# PureRingMod.net
KiCad netlist of a schematic drawn in EAGLE
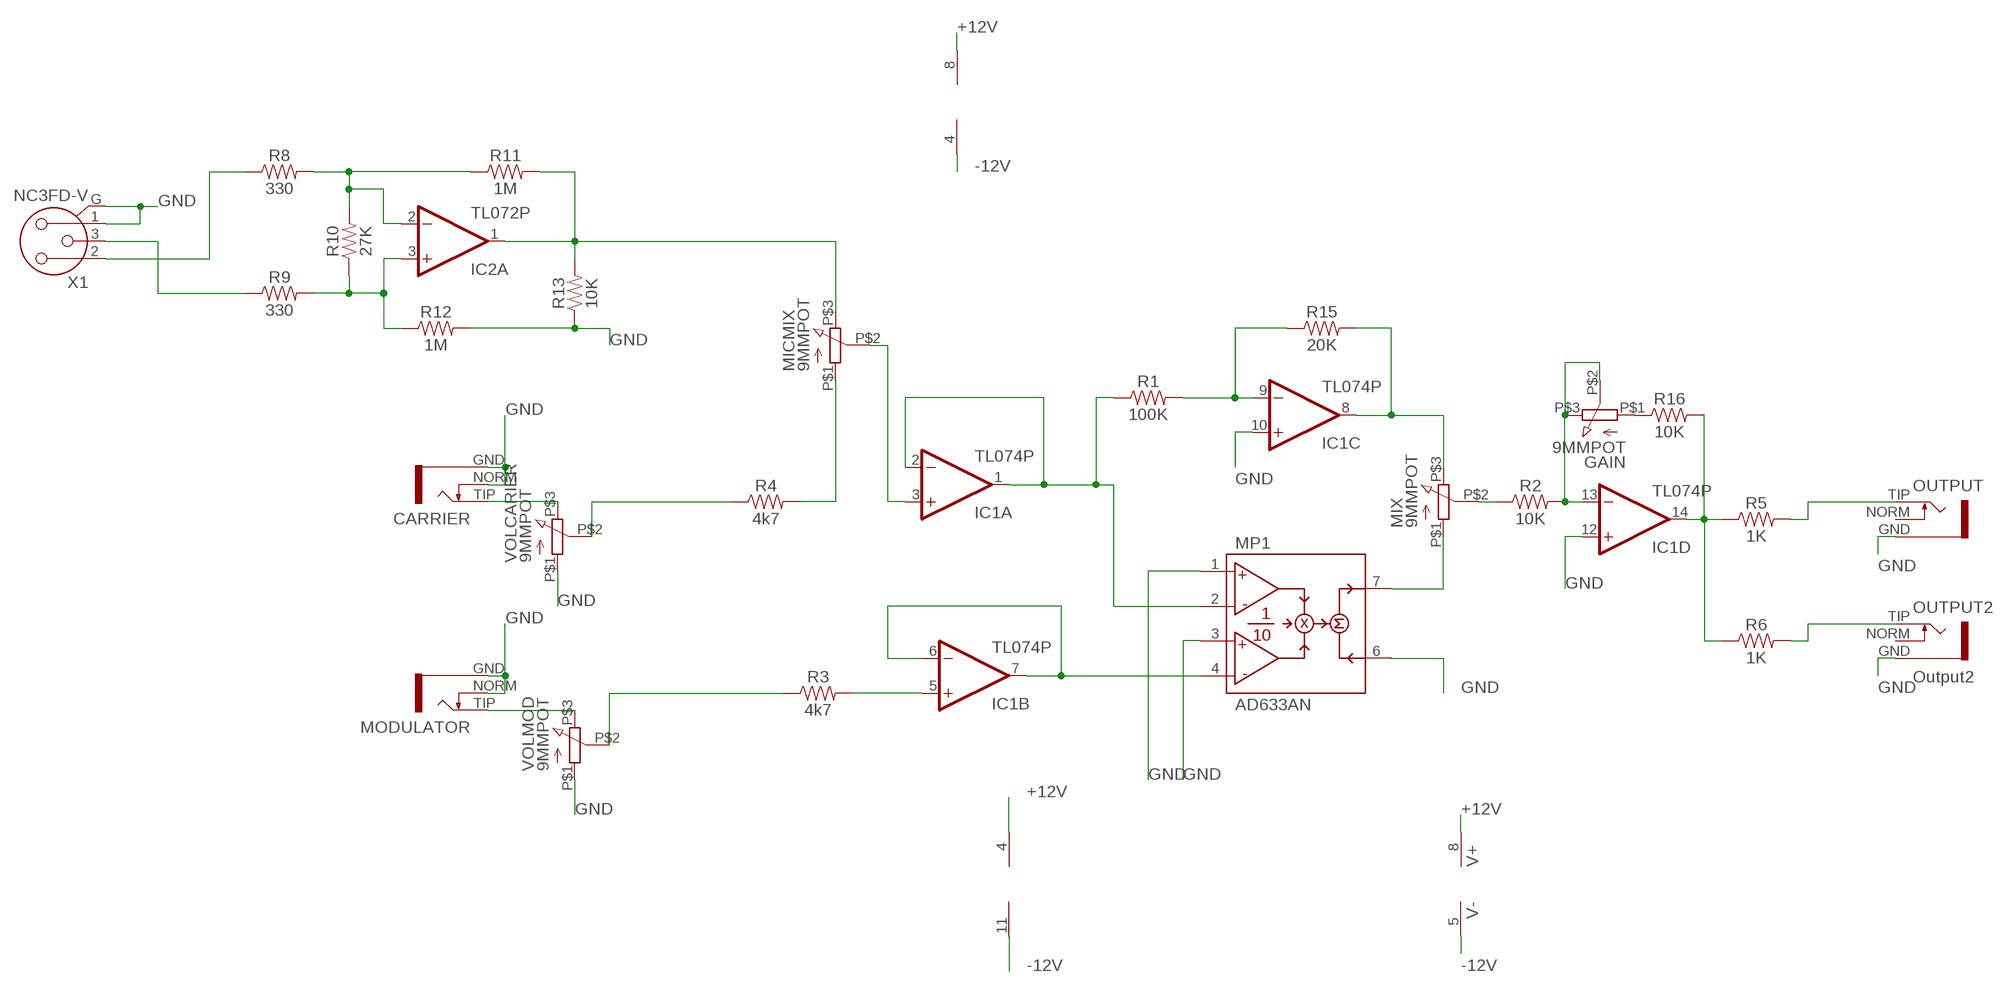
[diagram p0: schematic, sheet 1]
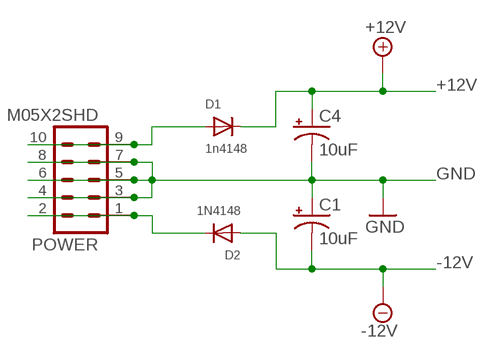
[diagram p1: schematic, sheet 2]

(export (version "E")
  (design (tool "Eeschema 10.0.6"))
  (components
    (comp (ref "C1")
      (value "10uF")
      (footprint "eagle-import:CPOL-RADIAL-2.5MM-5MM")
      (libsource (lib "eagle-import") (part "10UF-POLAR-RADIAL-2.5MM-25V-20%"))
    )
    (comp (ref "C4")
      (value "10uF")
      (footprint "eagle-import:CPOL-RADIAL-2.5MM-5MM")
      (libsource (lib "eagle-import") (part "10UF-POLAR-RADIAL-2.5MM-25V-20%"))
    )
    (comp (ref "D1")
      (value "1n4148")
      (footprint "eagle-import:DO-1N4148")
      (libsource (lib "eagle-import") (part "DIODEDO-1N4148"))
    )
    (comp (ref "D2")
      (value "1N4148")
      (footprint "eagle-import:DO-1N4148")
      (libsource (lib "eagle-import") (part "DIODEDO-1N4148"))
    )
    (comp (ref "POWER")
      (value "M05X2SHD")
      (footprint "eagle-import:2X5-SHROUDED")
      (libsource (lib "eagle-import") (part "M05X2SHD"))
    )
    (comp (ref "CARRIER")
      (value "S_JACK")
      (footprint "eagle-import:S_JACK")
      (libsource (lib "eagle-import") (part "S_JACK"))
    )
    (comp (ref "GAIN")
      (value "9MMPOT")
      (footprint "eagle-import:POT")
      (libsource (lib "eagle-import") (part "9MMPOT"))
    )
    (comp (ref "IC1")
      (value "TL074P")
      (footprint "eagle-import:DIL14")
      (libsource (lib "eagle-import") (part "TL074P"))
    )
    (comp (ref "IC2")
      (value "TL072P")
      (footprint "eagle-import:DIL08")
      (libsource (lib "eagle-import") (part "TL072P"))
    )
    (comp (ref "MICMIX")
      (value "9MMPOT")
      (footprint "eagle-import:POT")
      (libsource (lib "eagle-import") (part "9MMPOT"))
    )
    (comp (ref "MIX")
      (value "9MMPOT")
      (footprint "eagle-import:POT")
      (libsource (lib "eagle-import") (part "9MMPOT"))
    )
    (comp (ref "MODULATOR")
      (value "S_JACK")
      (footprint "eagle-import:S_JACK")
      (libsource (lib "eagle-import") (part "S_JACK"))
    )
    (comp (ref "MP1")
      (value "AD633AN")
      (footprint "eagle-import:DIL08")
      (libsource (lib "eagle-import") (part "AD633NA"))
    )
    (comp (ref "OUTPUT")
      (value "S_JACK")
      (footprint "eagle-import:S_JACK")
      (libsource (lib "eagle-import") (part "S_JACK"))
    )
    (comp (ref "OUTPUT2")
      (value "Output2")
      (footprint "eagle-import:S_JACK")
      (libsource (lib "eagle-import") (part "S_JACK"))
    )
    (comp (ref "R1")
      (value "100K")
      (footprint "eagle-import:AXIAL-0.3")
      (libsource (lib "eagle-import") (part "330OHM-HORIZ-1/10W-5%"))
    )
    (comp (ref "R2")
      (value "10K")
      (footprint "eagle-import:AXIAL-0.3")
      (libsource (lib "eagle-import") (part "330OHM-HORIZ-1/10W-5%"))
    )
    (comp (ref "R3")
      (value "4k7")
      (footprint "eagle-import:AXIAL-0.3")
      (libsource (lib "eagle-import") (part "330OHM-HORIZ-1/10W-5%"))
    )
    (comp (ref "R4")
      (value "4k7")
      (footprint "eagle-import:AXIAL-0.3")
      (libsource (lib "eagle-import") (part "330OHM-HORIZ-1/10W-5%"))
    )
    (comp (ref "R5")
      (value "1K")
      (footprint "eagle-import:AXIAL-0.3")
      (libsource (lib "eagle-import") (part "330OHM-HORIZ-1/10W-5%"))
    )
    (comp (ref "R6")
      (value "1K")
      (footprint "eagle-import:AXIAL-0.3")
      (libsource (lib "eagle-import") (part "330OHM-HORIZ-1/10W-5%"))
    )
    (comp (ref "R8")
      (value "330")
      (footprint "eagle-import:AXIAL-0.3")
      (libsource (lib "eagle-import") (part "330OHM-HORIZ-1/10W-5%"))
    )
    (comp (ref "R9")
      (value "330")
      (footprint "eagle-import:AXIAL-0.3")
      (libsource (lib "eagle-import") (part "330OHM-HORIZ-1/10W-5%"))
    )
    (comp (ref "R10")
      (value "27K")
      (footprint "eagle-import:AXIAL-0.3")
      (libsource (lib "eagle-import") (part "330OHM-HORIZ-1/10W-5%"))
    )
    (comp (ref "R11")
      (value "1M")
      (footprint "eagle-import:AXIAL-0.3")
      (libsource (lib "eagle-import") (part "330OHM-HORIZ-1/10W-5%"))
    )
    (comp (ref "R12")
      (value "1M")
      (footprint "eagle-import:AXIAL-0.3")
      (libsource (lib "eagle-import") (part "330OHM-HORIZ-1/10W-5%"))
    )
    (comp (ref "R13")
      (value "10K")
      (footprint "eagle-import:AXIAL-0.3")
      (libsource (lib "eagle-import") (part "330OHM-HORIZ-1/10W-5%"))
    )
    (comp (ref "R15")
      (value "20K")
      (footprint "eagle-import:AXIAL-0.3")
      (libsource (lib "eagle-import") (part "330OHM-HORIZ-1/10W-5%"))
    )
    (comp (ref "R16")
      (value "10K")
      (footprint "eagle-import:AXIAL-0.3")
      (libsource (lib "eagle-import") (part "330OHM-HORIZ-1/10W-5%"))
    )
    (comp (ref "VOLCARIER")
      (value "9MMPOT")
      (footprint "eagle-import:POT")
      (libsource (lib "eagle-import") (part "9MMPOT"))
    )
    (comp (ref "VOLMOD")
      (value "9MMPOT")
      (footprint "eagle-import:POT")
      (libsource (lib "eagle-import") (part "9MMPOT"))
    )
    (comp (ref "X1")
      (value "NC3FD-V")
      (footprint "eagle-import:NC3FD-V")
      (fields (field (name "MF") "FARNELL") (field (name "MPN") "NC3FDV") (field (name "RS-PART") "448-244"))
      (libsource (lib "eagle-import") (part "NC3FD-V"))
    )
  )
  (nets
    (net (code "1") (name "+12V") (class "Default")
      (node (ref "C4") (pin "1") (pinfunction "+_1") (pintype "passive"))
      (node (ref "D1") (pin "C") (pinfunction "C_C") (pintype "passive"))
      (node (ref "IC1") (pin "4") (pinfunction "V+_4") (pintype "power_in"))
      (node (ref "IC2") (pin "8") (pinfunction "V+_8") (pintype "power_in"))
      (node (ref "MP1") (pin "8") (pinfunction "V+_8") (pintype "power_in"))
    )
    (net (code "2") (name "-12V") (class "Default")
      (node (ref "C1") (pin "2") (pinfunction "-_2") (pintype "passive"))
      (node (ref "D2") (pin "A") (pinfunction "A_A") (pintype "passive"))
      (node (ref "IC1") (pin "11") (pinfunction "V-_11") (pintype "power_in"))
      (node (ref "IC2") (pin "4") (pinfunction "V-_4") (pintype "power_in"))
      (node (ref "MP1") (pin "5") (pinfunction "V-_5") (pintype "power_in"))
    )
    (net (code "3") (name "GND") (class "Default")
      (node (ref "C1") (pin "1") (pinfunction "+_1") (pintype "passive"))
      (node (ref "C4") (pin "2") (pinfunction "-_2") (pintype "passive"))
      (node (ref "CARRIER") (pin "GND") (pinfunction "GND_GND") (pintype "passive"))
      (node (ref "CARRIER") (pin "NORM") (pinfunction "NORM_NORM") (pintype "passive"))
      (node (ref "IC1") (pin "10") (pinfunction "+IN_10") (pintype "input"))
      (node (ref "IC1") (pin "12") (pinfunction "+IN_12") (pintype "input"))
      (node (ref "MODULATOR") (pin "GND") (pinfunction "GND_GND") (pintype "passive"))
      (node (ref "MODULATOR") (pin "NORM") (pinfunction "NORM_NORM") (pintype "passive"))
      (node (ref "MP1") (pin "1") (pinfunction "X1_1") (pintype "input"))
      (node (ref "MP1") (pin "3") (pinfunction "Y1_3") (pintype "input"))
      (node (ref "MP1") (pin "6") (pinfunction "Z_6") (pintype "input"))
      (node (ref "OUTPUT") (pin "GND") (pinfunction "GND_GND") (pintype "passive"))
      (node (ref "OUTPUT2") (pin "GND") (pinfunction "GND_GND") (pintype "passive"))
      (node (ref "POWER") (pin "3") (pinfunction "3_3") (pintype "passive"))
      (node (ref "POWER") (pin "4") (pinfunction "4_4") (pintype "passive"))
      (node (ref "POWER") (pin "5") (pinfunction "5_5") (pintype "passive"))
      (node (ref "POWER") (pin "6") (pinfunction "6_6") (pintype "passive"))
      (node (ref "POWER") (pin "7") (pinfunction "7_7") (pintype "passive"))
      (node (ref "POWER") (pin "8") (pinfunction "8_8") (pintype "passive"))
      (node (ref "R12") (pin "P$2") (pinfunction "2_P$2") (pintype "passive"))
      (node (ref "R13") (pin "P$1") (pinfunction "1_P$1") (pintype "passive"))
      (node (ref "VOLCARIER") (pin "P$1") (pinfunction "1_P$1") (pintype "passive"))
      (node (ref "VOLMOD") (pin "P$1") (pinfunction "1_P$1") (pintype "passive"))
      (node (ref "X1") (pin "1") (pinfunction "2_1") (pintype "passive"))
      (node (ref "X1") (pin "G") (pinfunction "G_G") (pintype "passive"))
    )
    (net (code "4") (name "Net-(D1-PadA)") (class "Default")
      (node (ref "D1") (pin "A") (pinfunction "A_A") (pintype "passive"))
      (node (ref "POWER") (pin "10") (pinfunction "10_10") (pintype "passive"))
      (node (ref "POWER") (pin "9") (pinfunction "9_9") (pintype "passive"))
    )
    (net (code "5") (name "Net-(D2-PadC)") (class "Default")
      (node (ref "D2") (pin "C") (pinfunction "C_C") (pintype "passive"))
      (node (ref "POWER") (pin "1") (pinfunction "1_1") (pintype "passive"))
      (node (ref "POWER") (pin "2") (pinfunction "2_2") (pintype "passive"))
    )
    (net (code "6") (name "Net-(GAIN-1)") (class "Default")
      (node (ref "GAIN") (pin "P$1") (pinfunction "1_P$1") (pintype "passive"))
      (node (ref "R16") (pin "P$1") (pinfunction "1_P$1") (pintype "passive"))
    )
    (net (code "7") (name "Net-(GAIN-2)") (class "Default")
      (node (ref "GAIN") (pin "P$2") (pinfunction "2_P$2") (pintype "passive"))
      (node (ref "GAIN") (pin "P$3") (pinfunction "3_P$3") (pintype "passive"))
      (node (ref "IC1") (pin "13") (pinfunction "-IN_13") (pintype "input"))
      (node (ref "R2") (pin "P$2") (pinfunction "2_P$2") (pintype "passive"))
    )
    (net (code "8") (name "Net-(IC1A-+IN)") (class "Default")
      (node (ref "IC1") (pin "3") (pinfunction "+IN_3") (pintype "input"))
      (node (ref "MICMIX") (pin "P$2") (pinfunction "2_P$2") (pintype "passive"))
    )
    (net (code "9") (name "Net-(IC1A--IN)") (class "Default")
      (node (ref "IC1") (pin "1") (pinfunction "OUT_1") (pintype "output"))
      (node (ref "IC1") (pin "2") (pinfunction "-IN_2") (pintype "input"))
      (node (ref "MP1") (pin "2") (pinfunction "X2_2") (pintype "input"))
      (node (ref "R1") (pin "P$1") (pinfunction "1_P$1") (pintype "passive"))
    )
    (net (code "10") (name "Net-(IC1B-+IN)") (class "Default")
      (node (ref "IC1") (pin "5") (pinfunction "+IN_5") (pintype "input"))
      (node (ref "R3") (pin "P$2") (pinfunction "2_P$2") (pintype "passive"))
    )
    (net (code "11") (name "Net-(IC1B--IN)") (class "Default")
      (node (ref "IC1") (pin "6") (pinfunction "-IN_6") (pintype "input"))
      (node (ref "IC1") (pin "7") (pinfunction "OUT_7") (pintype "output"))
      (node (ref "MP1") (pin "4") (pinfunction "Y2_4") (pintype "input"))
    )
    (net (code "12") (name "Net-(IC1C--IN)") (class "Default")
      (node (ref "IC1") (pin "9") (pinfunction "-IN_9") (pintype "input"))
      (node (ref "R1") (pin "P$2") (pinfunction "2_P$2") (pintype "passive"))
      (node (ref "R15") (pin "P$1") (pinfunction "1_P$1") (pintype "passive"))
    )
    (net (code "13") (name "Net-(IC1C-OUT)") (class "Default")
      (node (ref "IC1") (pin "8") (pinfunction "OUT_8") (pintype "output"))
      (node (ref "MIX") (pin "P$3") (pinfunction "3_P$3") (pintype "passive"))
      (node (ref "R15") (pin "P$2") (pinfunction "2_P$2") (pintype "passive"))
    )
    (net (code "14") (name "Net-(IC1D-OUT)") (class "Default")
      (node (ref "IC1") (pin "14") (pinfunction "OUT_14") (pintype "output"))
      (node (ref "R16") (pin "P$2") (pinfunction "2_P$2") (pintype "passive"))
      (node (ref "R5") (pin "P$1") (pinfunction "1_P$1") (pintype "passive"))
      (node (ref "R6") (pin "P$1") (pinfunction "1_P$1") (pintype "passive"))
    )
    (net (code "15") (name "Net-(IC2A-+IN)") (class "Default")
      (node (ref "IC2") (pin "3") (pinfunction "+IN_3") (pintype "input"))
      (node (ref "R10") (pin "P$1") (pinfunction "1_P$1") (pintype "passive"))
      (node (ref "R12") (pin "P$1") (pinfunction "1_P$1") (pintype "passive"))
      (node (ref "R9") (pin "P$2") (pinfunction "2_P$2") (pintype "passive"))
    )
    (net (code "16") (name "Net-(IC2A--IN)") (class "Default")
      (node (ref "IC2") (pin "2") (pinfunction "-IN_2") (pintype "input"))
      (node (ref "R10") (pin "P$2") (pinfunction "2_P$2") (pintype "passive"))
      (node (ref "R11") (pin "P$1") (pinfunction "1_P$1") (pintype "passive"))
      (node (ref "R8") (pin "P$2") (pinfunction "2_P$2") (pintype "passive"))
    )
    (net (code "17") (name "Net-(IC2A-OUT)") (class "Default")
      (node (ref "IC2") (pin "1") (pinfunction "OUT_1") (pintype "output"))
      (node (ref "MICMIX") (pin "P$3") (pinfunction "3_P$3") (pintype "passive"))
      (node (ref "R11") (pin "P$2") (pinfunction "2_P$2") (pintype "passive"))
      (node (ref "R13") (pin "P$2") (pinfunction "2_P$2") (pintype "passive"))
    )
    (net (code "18") (name "Net-(MICMIX-1)") (class "Default")
      (node (ref "MICMIX") (pin "P$1") (pinfunction "1_P$1") (pintype "passive"))
      (node (ref "R4") (pin "P$2") (pinfunction "2_P$2") (pintype "passive"))
    )
    (net (code "19") (name "Net-(MIX-1)") (class "Default")
      (node (ref "MIX") (pin "P$1") (pinfunction "1_P$1") (pintype "passive"))
      (node (ref "MP1") (pin "7") (pinfunction "W_7") (pintype "output"))
    )
    (net (code "20") (name "Net-(MIX-2)") (class "Default")
      (node (ref "MIX") (pin "P$2") (pinfunction "2_P$2") (pintype "passive"))
      (node (ref "R2") (pin "P$1") (pinfunction "1_P$1") (pintype "passive"))
    )
    (net (code "21") (name "Net-(R3-1)") (class "Default")
      (node (ref "R3") (pin "P$1") (pinfunction "1_P$1") (pintype "passive"))
      (node (ref "VOLMOD") (pin "P$2") (pinfunction "2_P$2") (pintype "passive"))
    )
    (net (code "22") (name "Net-(R4-1)") (class "Default")
      (node (ref "R4") (pin "P$1") (pinfunction "1_P$1") (pintype "passive"))
      (node (ref "VOLCARIER") (pin "P$2") (pinfunction "2_P$2") (pintype "passive"))
    )
    (net (code "23") (name "Net-(R5-2)") (class "Default")
      (node (ref "OUTPUT") (pin "TIP") (pinfunction "TIP_TIP") (pintype "passive"))
      (node (ref "R5") (pin "P$2") (pinfunction "2_P$2") (pintype "passive"))
    )
    (net (code "24") (name "Net-(R6-2)") (class "Default")
      (node (ref "OUTPUT2") (pin "TIP") (pinfunction "TIP_TIP") (pintype "passive"))
      (node (ref "R6") (pin "P$2") (pinfunction "2_P$2") (pintype "passive"))
    )
    (net (code "25") (name "Net-(R8-1)") (class "Default")
      (node (ref "R8") (pin "P$1") (pinfunction "1_P$1") (pintype "passive"))
      (node (ref "X1") (pin "2") (pinfunction "1_2") (pintype "passive"))
    )
    (net (code "26") (name "Net-(R9-1)") (class "Default")
      (node (ref "R9") (pin "P$1") (pinfunction "1_P$1") (pintype "passive"))
      (node (ref "X1") (pin "3") (pinfunction "3_3") (pintype "passive"))
    )
    (net (code "27") (name "Net-(VOLCARIER-3)") (class "Default")
      (node (ref "CARRIER") (pin "TIP") (pinfunction "TIP_TIP") (pintype "passive"))
      (node (ref "VOLCARIER") (pin "P$3") (pinfunction "3_P$3") (pintype "passive"))
    )
    (net (code "28") (name "Net-(VOLMOD-3)") (class "Default")
      (node (ref "MODULATOR") (pin "TIP") (pinfunction "TIP_TIP") (pintype "passive"))
      (node (ref "VOLMOD") (pin "P$3") (pinfunction "3_P$3") (pintype "passive"))
    )
    (net (code "29") (name "unconnected-(OUTPUT-PadNORM)") (class "Default")
      (node (ref "OUTPUT") (pin "NORM") (pinfunction "NORM_NORM") (pintype "passive"))
    )
    (net (code "30") (name "unconnected-(OUTPUT2-PadNORM)") (class "Default")
      (node (ref "OUTPUT2") (pin "NORM") (pinfunction "NORM_NORM") (pintype "passive"))
    )
  )
)
